# breakout.net
KiCad netlist of a schematic drawn in EAGLE
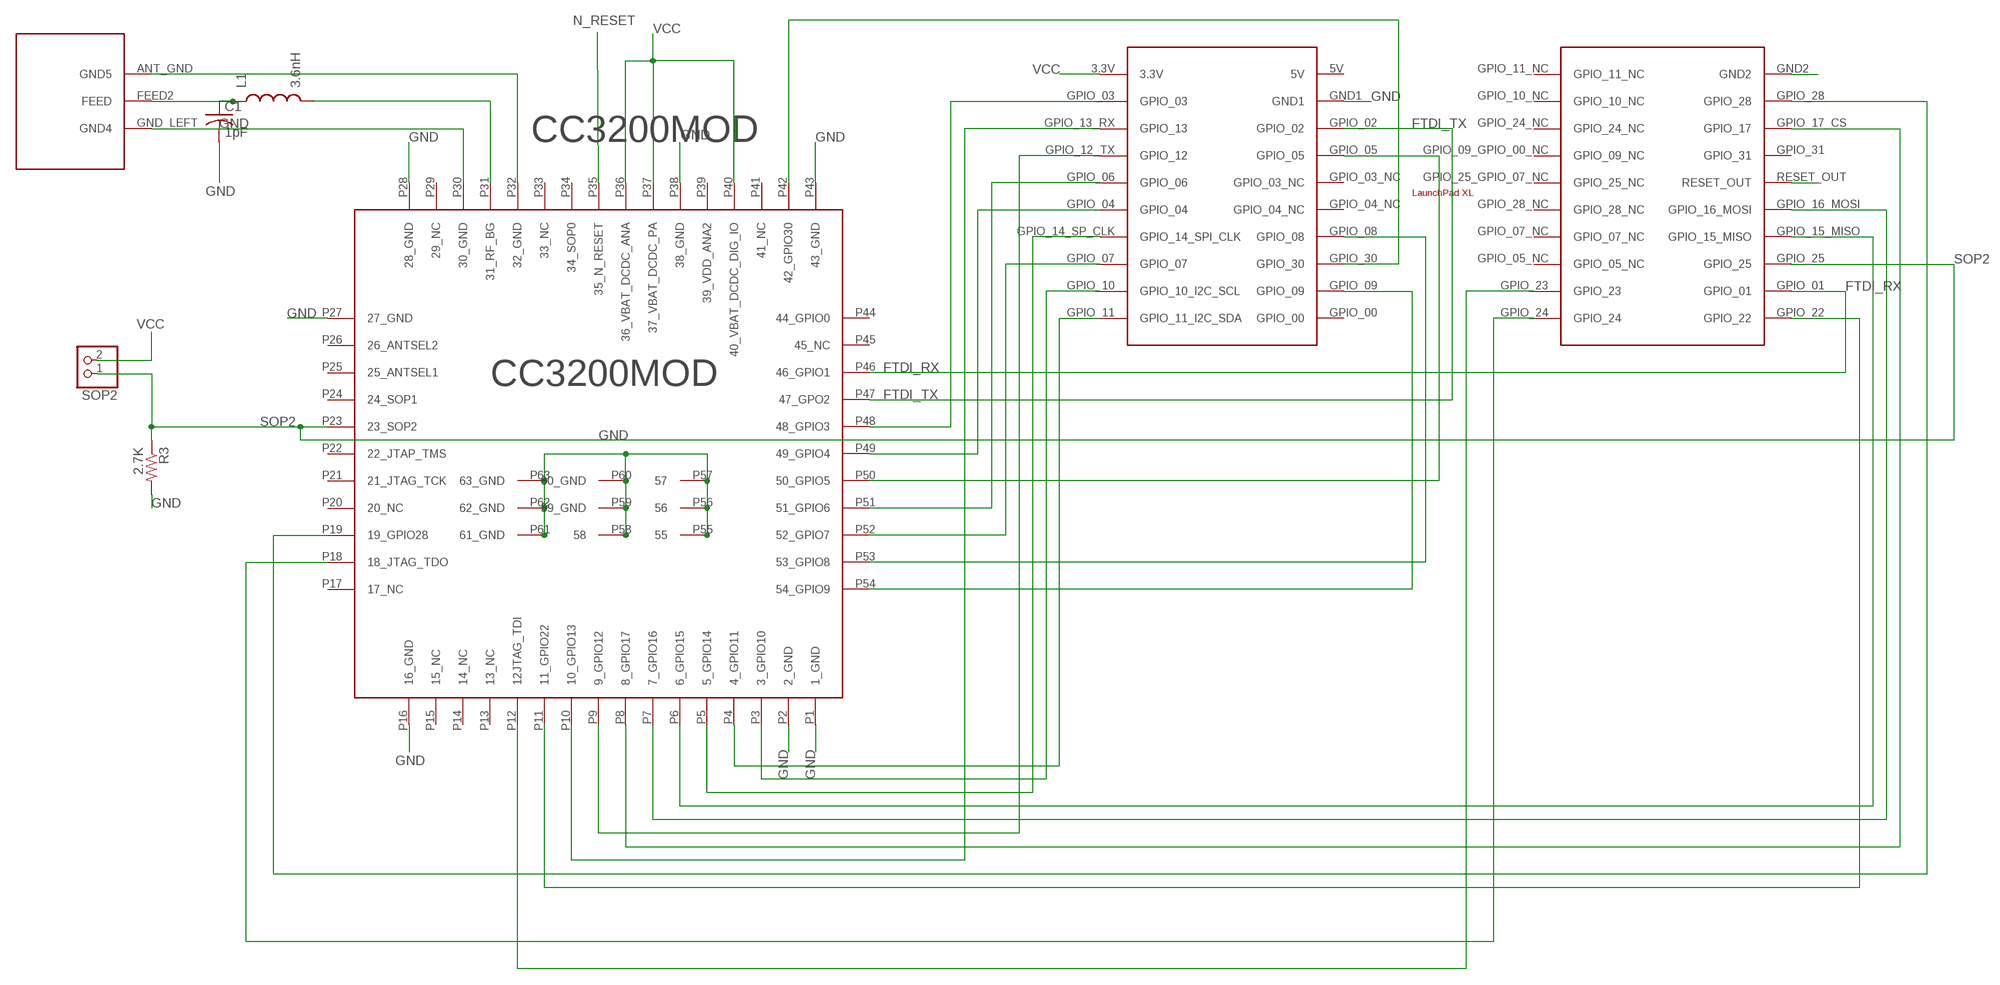
[diagram p0: schematic, sheet 1]
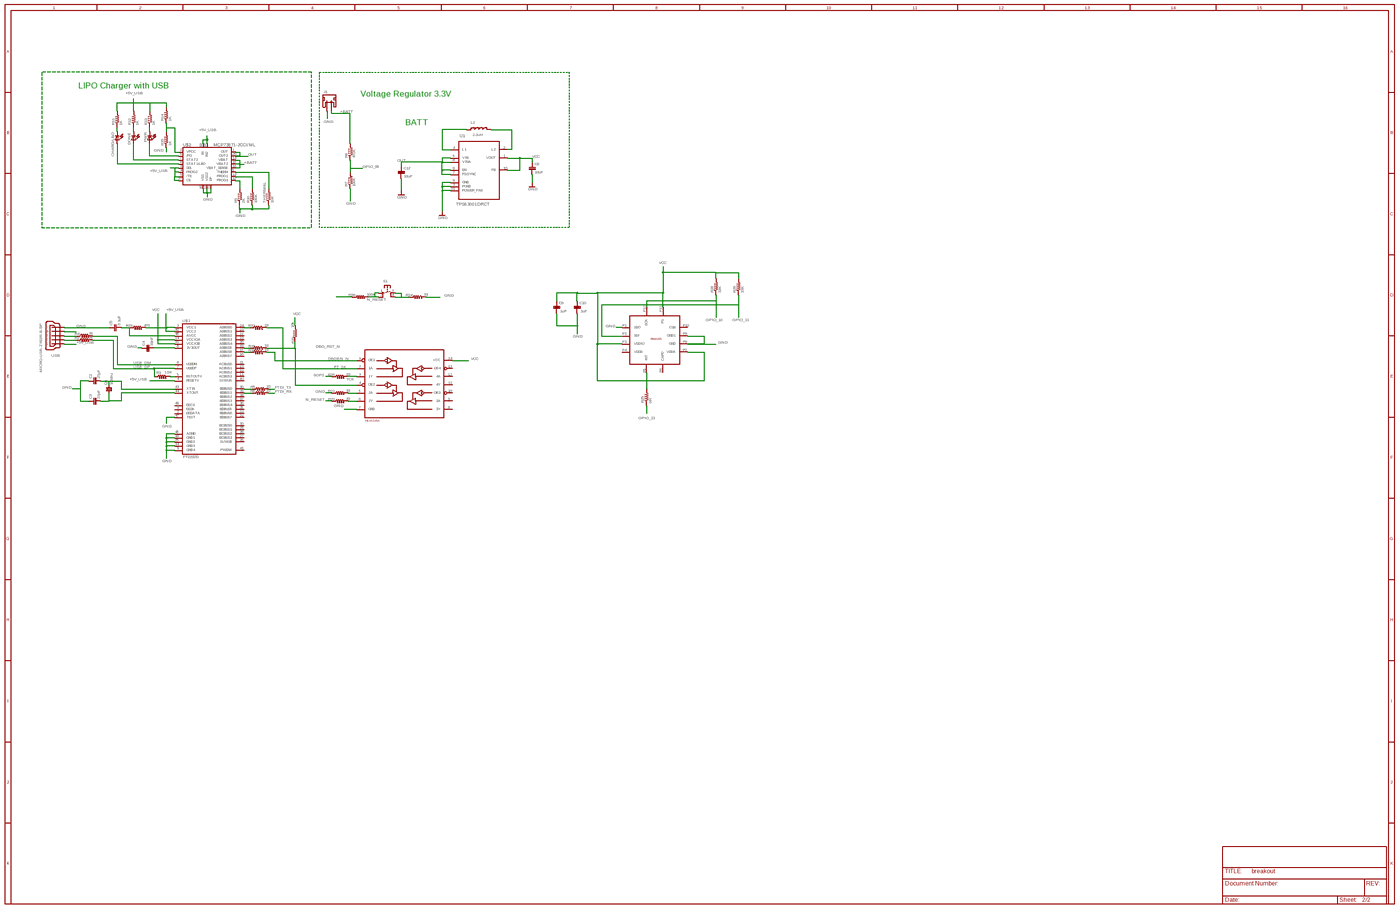
[diagram p1: schematic, sheet 2, overview]
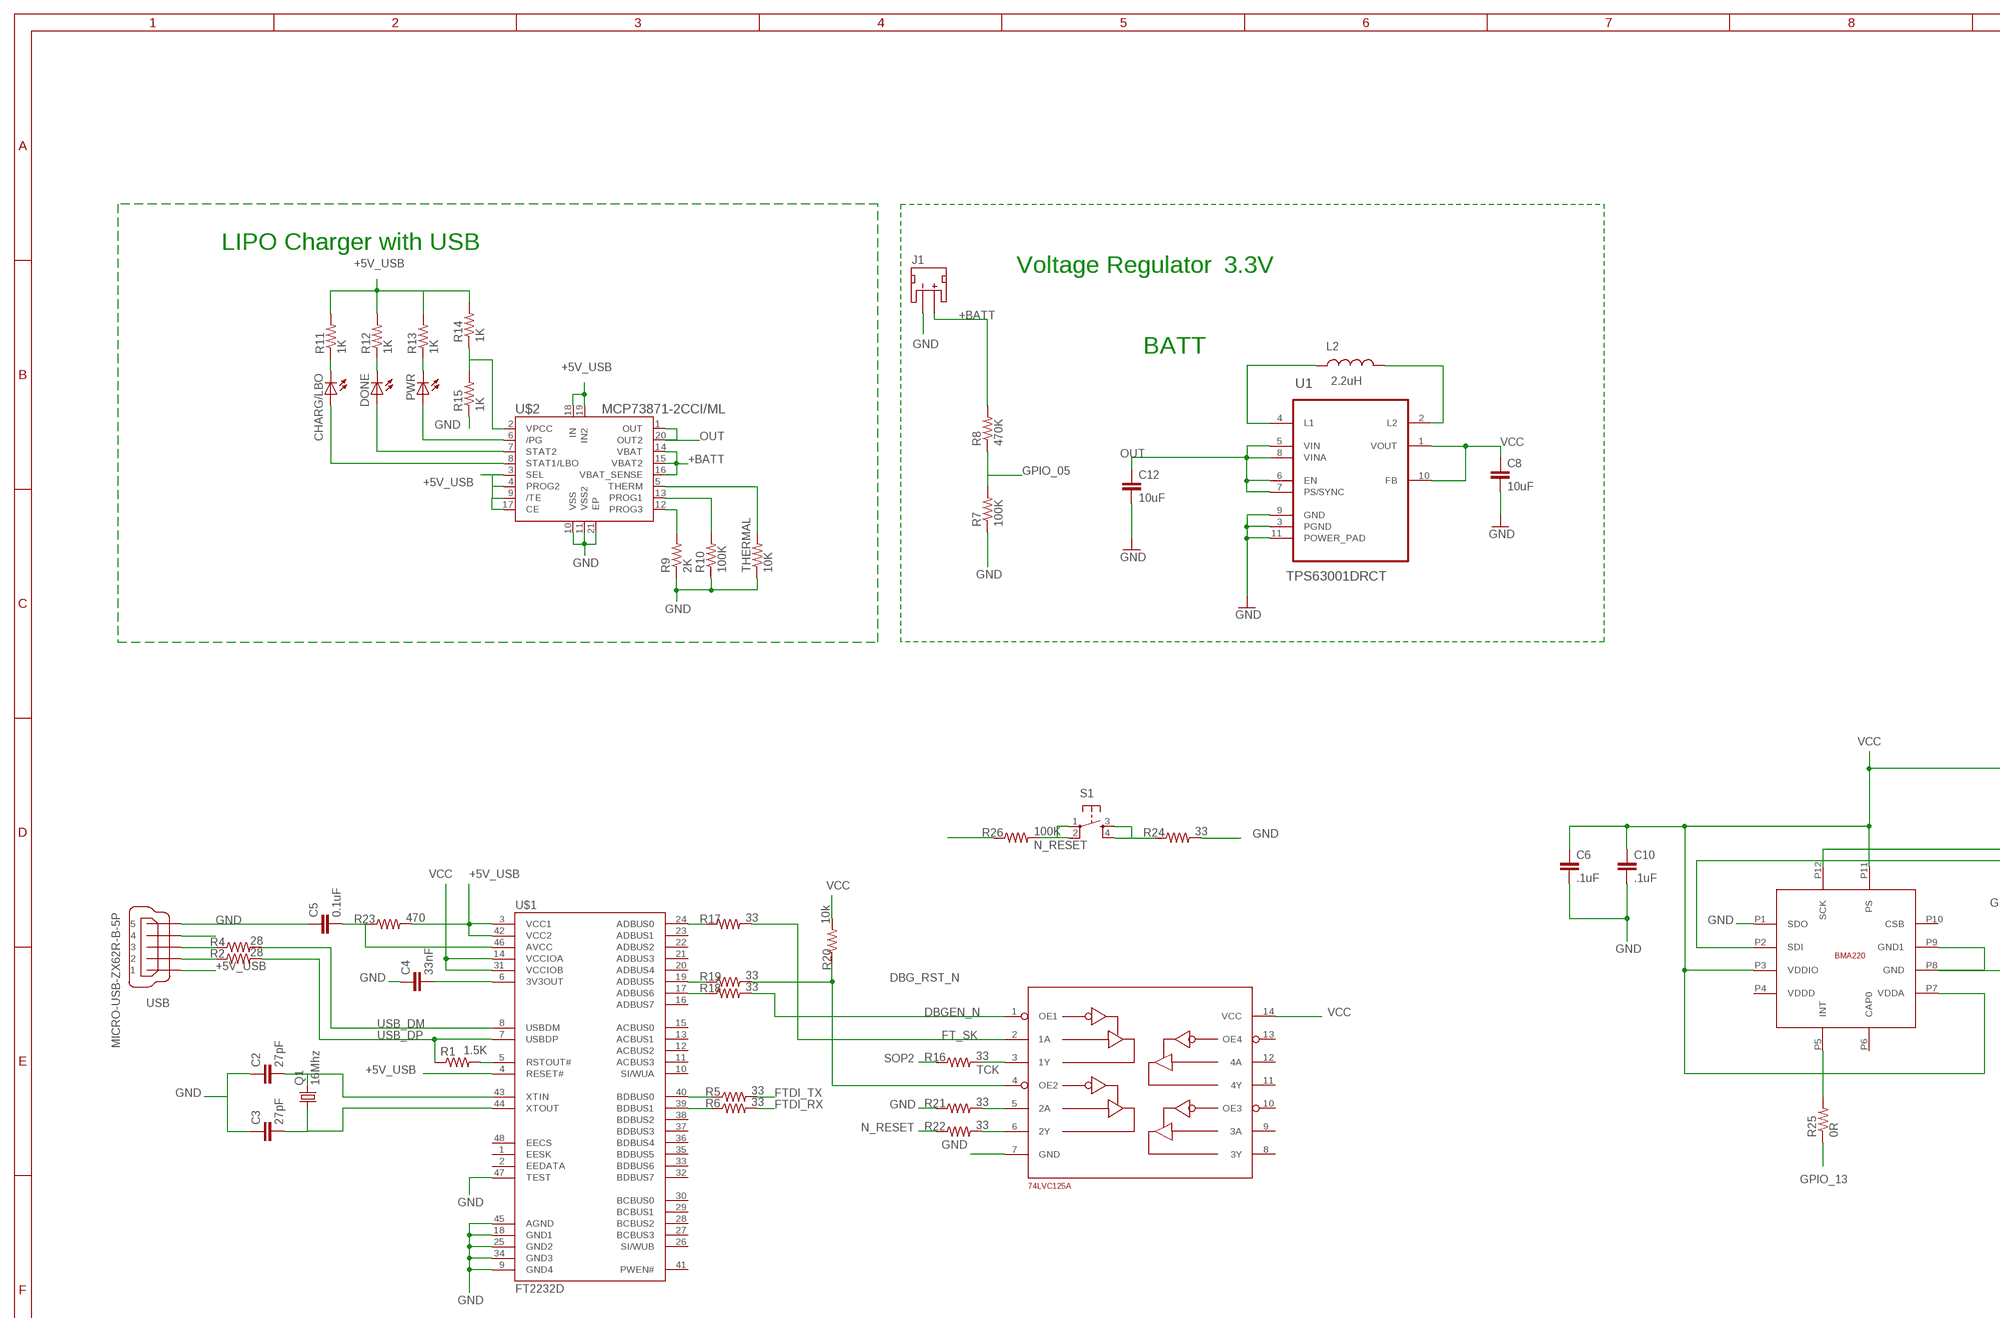
[diagram p2: schematic, sheet 2, part 1 of 4]
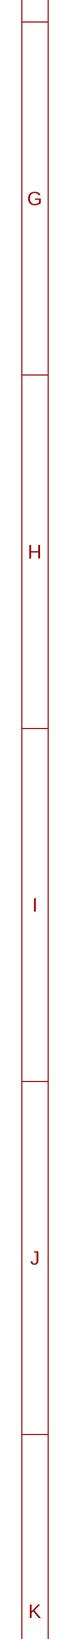
[diagram p3: schematic, sheet 2, part 2 of 4]
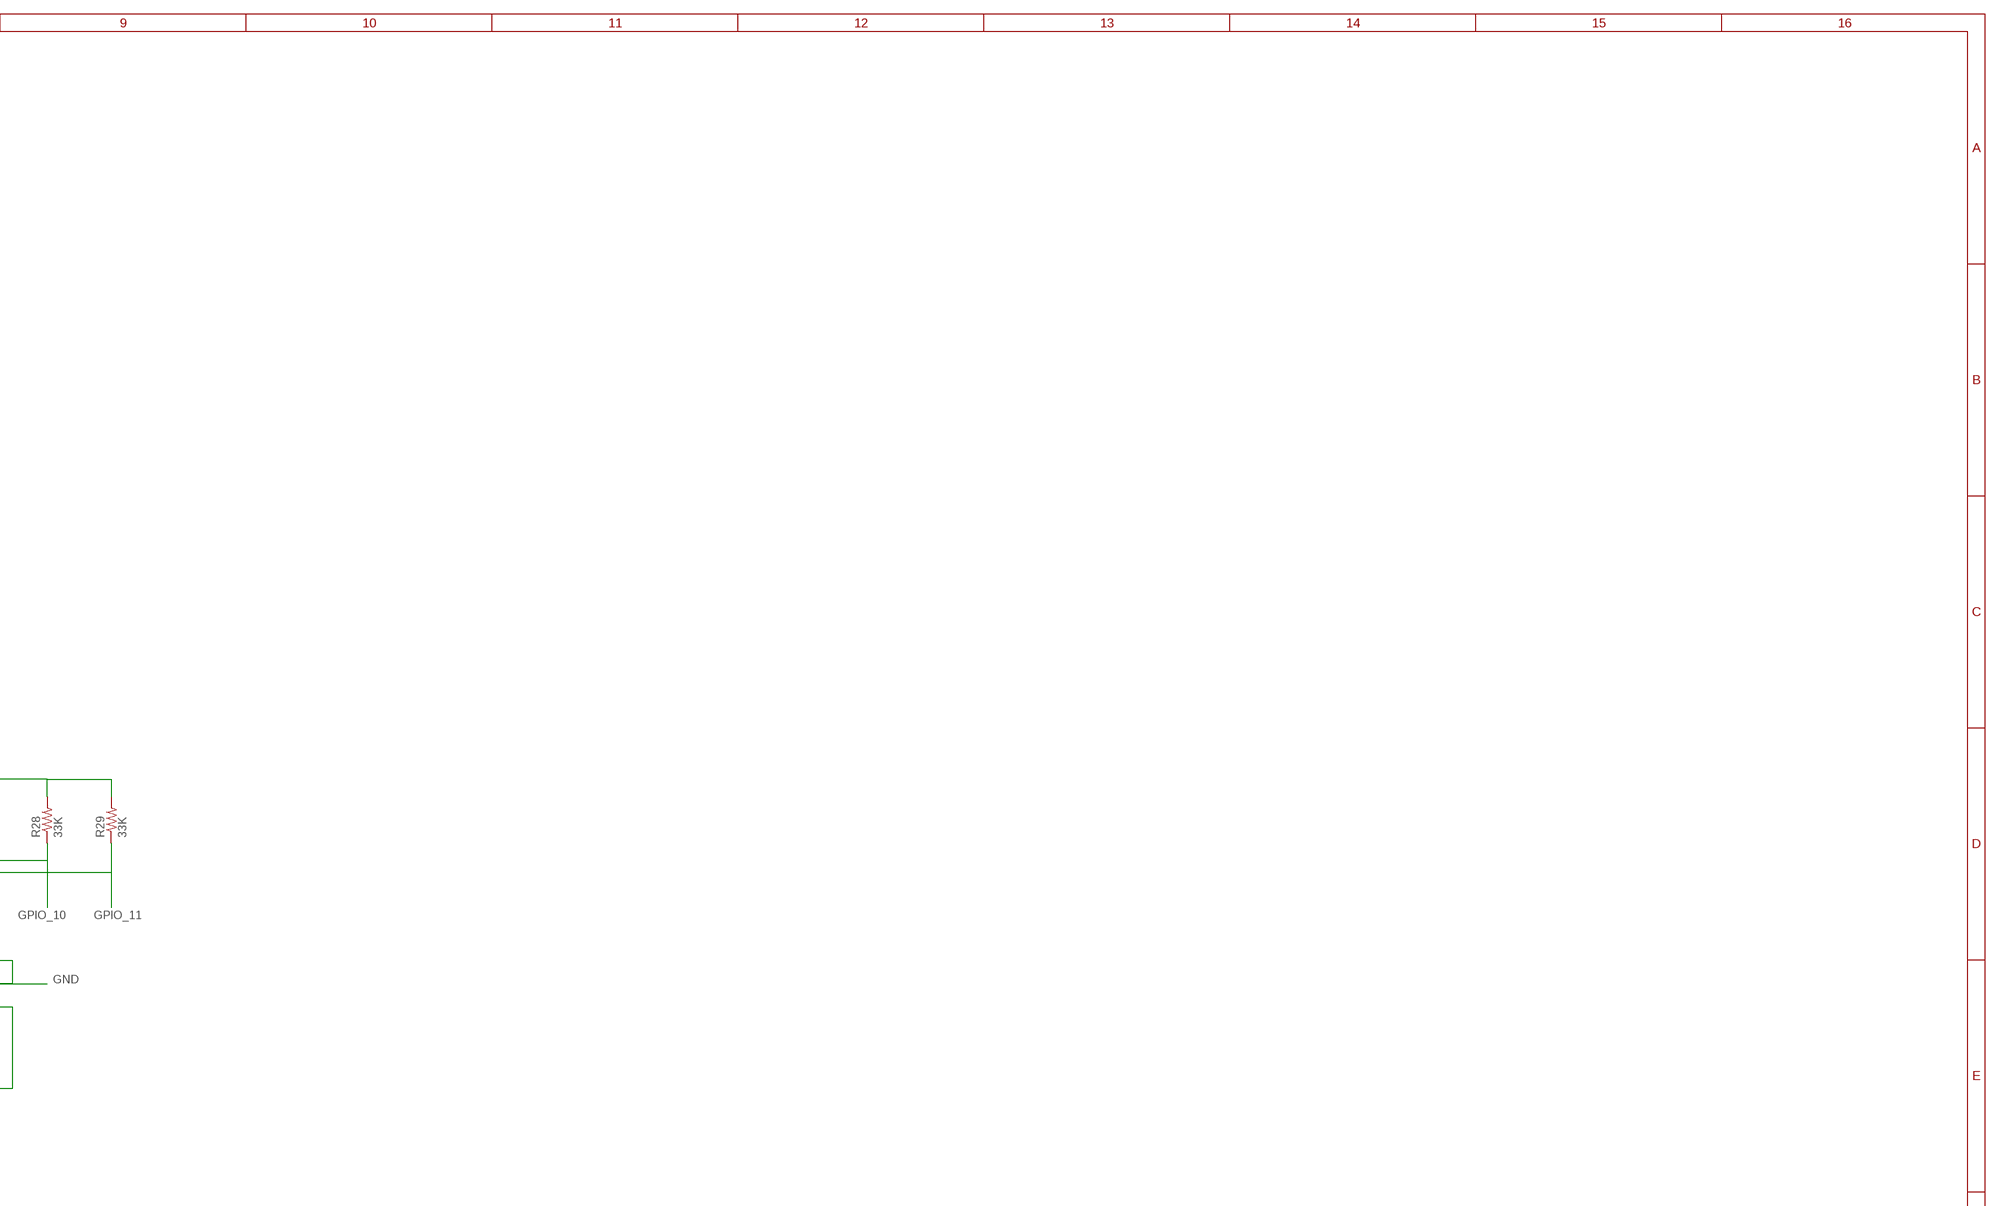
[diagram p4: schematic, sheet 2, part 3 of 4]
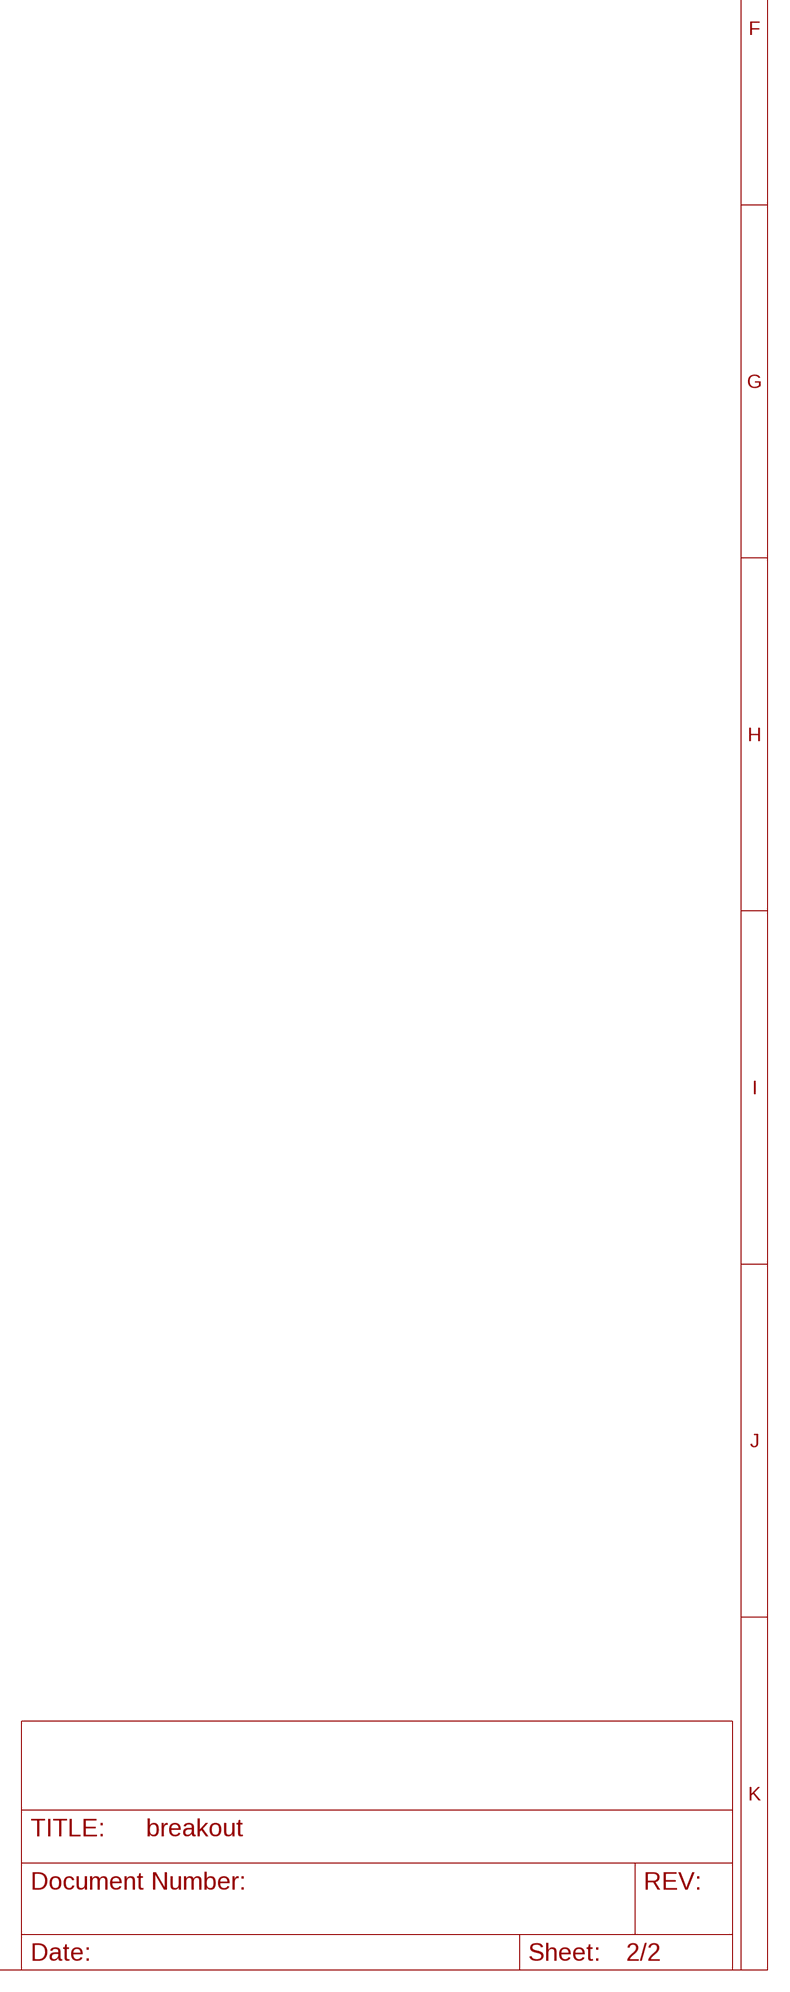
[diagram p5: schematic, sheet 2, part 4 of 4]

(export (version "E")
  (design (tool "Eeschema 10.0.6"))
  (components
    (comp (ref "C2")
      (value "27pF")
      (footprint "eagle-import:0402-CAP")
      (libsource (lib "eagle-import") (part "SparkFun-Passives_CAP0402-CAP"))
    )
    (comp (ref "C3")
      (value "27pF")
      (footprint "eagle-import:0402-CAP")
      (libsource (lib "eagle-import") (part "SparkFun-Passives_CAP0402-CAP"))
    )
    (comp (ref "C4")
      (value "33nF")
      (footprint "eagle-import:0402-CAP")
      (libsource (lib "eagle-import") (part "SparkFun-Passives_CAP0402-CAP"))
    )
    (comp (ref "C5")
      (value "0.1uF")
      (footprint "eagle-import:0402-CAP")
      (libsource (lib "eagle-import") (part "SparkFun-Passives_CAP0402-CAP"))
    )
    (comp (ref "C6")
      (value ".1uF")
      (footprint "eagle-import:0402-CAP")
      (libsource (lib "eagle-import") (part "CAP0402-CAP"))
    )
    (comp (ref "C8")
      (value "10uF")
      (footprint "eagle-import:C0603")
      (libsource (lib "eagle-import") (part "C-EUC0603"))
    )
    (comp (ref "C10")
      (value ".1uF")
      (footprint "eagle-import:0402-CAP")
      (libsource (lib "eagle-import") (part "CAP0402-CAP"))
    )
    (comp (ref "C12")
      (value "10uF")
      (footprint "eagle-import:C0603")
      (libsource (lib "eagle-import") (part "C-EUC0603"))
    )
    (comp (ref "CHARG/LBO")
      (value "LEDSML0603")
      (footprint "eagle-import:SML0603")
      (libsource (lib "eagle-import") (part "LEDSML0603"))
    )
    (comp (ref "DONE")
      (value "LEDSML0603")
      (footprint "eagle-import:SML0603")
      (libsource (lib "eagle-import") (part "LEDSML0603"))
    )
    (comp (ref "J1")
      (value "JST_2MM_MALE")
      (footprint "eagle-import:JST-2-SMD")
      (libsource (lib "eagle-import") (part "JST_2MM_MALE"))
    )
    (comp (ref "L2")
      (value "2.2uH")
      (footprint "eagle-import:0805")
      (libsource (lib "eagle-import") (part "INDUCTOR0805"))
    )
    (comp (ref "PWR")
      (value "LEDSML0603")
      (footprint "eagle-import:SML0603")
      (libsource (lib "eagle-import") (part "LEDSML0603"))
    )
    (comp (ref "Q1")
      (value "16Mhz")
      (footprint "eagle-import:TC26H")
      (libsource (lib "eagle-import") (part "CRYSTALTC26H"))
    )
    (comp (ref "R1")
      (value "1.5K")
      (footprint "eagle-import:0603-RES")
      (libsource (lib "eagle-import") (part "RESISTOR0603"))
    )
    (comp (ref "R2")
      (value "28")
      (footprint "eagle-import:0603-RES")
      (libsource (lib "eagle-import") (part "RESISTOR0603-RES"))
    )
    (comp (ref "R4")
      (value "28")
      (footprint "eagle-import:0603-RES")
      (libsource (lib "eagle-import") (part "RESISTOR0603-RES"))
    )
    (comp (ref "R5")
      (value "33")
      (footprint "eagle-import:0603-RES")
      (libsource (lib "eagle-import") (part "RESISTOR0603"))
    )
    (comp (ref "R6")
      (value "33")
      (footprint "eagle-import:0603-RES")
      (libsource (lib "eagle-import") (part "RESISTOR0603"))
    )
    (comp (ref "R7")
      (value "100K")
      (footprint "eagle-import:0603-RES")
      (libsource (lib "eagle-import") (part "RESISTOR0603"))
    )
    (comp (ref "R8")
      (value "470K")
      (footprint "eagle-import:0603-RES")
      (libsource (lib "eagle-import") (part "RESISTOR0603"))
    )
    (comp (ref "R9")
      (value "2K")
      (footprint "eagle-import:0603-RES")
      (libsource (lib "eagle-import") (part "RESISTOR0603-RES"))
    )
    (comp (ref "R10")
      (value "100K")
      (footprint "eagle-import:0603-RES")
      (libsource (lib "eagle-import") (part "RESISTOR0603-RES"))
    )
    (comp (ref "R11")
      (value "1K")
      (footprint "eagle-import:0603-RES")
      (libsource (lib "eagle-import") (part "RESISTOR0603-RES"))
    )
    (comp (ref "R12")
      (value "1K")
      (footprint "eagle-import:0603-RES")
      (libsource (lib "eagle-import") (part "RESISTOR0603-RES"))
    )
    (comp (ref "R13")
      (value "1K")
      (footprint "eagle-import:0603-RES")
      (libsource (lib "eagle-import") (part "RESISTOR0603-RES"))
    )
    (comp (ref "R14")
      (value "1K")
      (footprint "eagle-import:0603-RES")
      (libsource (lib "eagle-import") (part "RESISTOR0603-RES"))
    )
    (comp (ref "R15")
      (value "1K")
      (footprint "eagle-import:0603-RES")
      (libsource (lib "eagle-import") (part "RESISTOR0603-RES"))
    )
    (comp (ref "R16")
      (value "33")
      (footprint "eagle-import:0603-RES")
      (libsource (lib "eagle-import") (part "RESISTOR0603"))
    )
    (comp (ref "R17")
      (value "33")
      (footprint "eagle-import:0603-RES")
      (libsource (lib "eagle-import") (part "RESISTOR0603"))
    )
    (comp (ref "R18")
      (value "33")
      (footprint "eagle-import:0603-RES")
      (libsource (lib "eagle-import") (part "RESISTOR0603"))
    )
    (comp (ref "R19")
      (value "33")
      (footprint "eagle-import:0603-RES")
      (libsource (lib "eagle-import") (part "RESISTOR0603"))
    )
    (comp (ref "R20")
      (value "10k")
      (footprint "eagle-import:0603-RES")
      (libsource (lib "eagle-import") (part "RESISTOR0603"))
    )
    (comp (ref "R21")
      (value "33")
      (footprint "eagle-import:0603-RES")
      (libsource (lib "eagle-import") (part "RESISTOR0603"))
    )
    (comp (ref "R22")
      (value "33")
      (footprint "eagle-import:0603-RES")
      (libsource (lib "eagle-import") (part "RESISTOR0603"))
    )
    (comp (ref "R23")
      (value "470")
      (footprint "eagle-import:0603-RES")
      (libsource (lib "eagle-import") (part "RESISTOR0603"))
    )
    (comp (ref "R24")
      (value "33")
      (footprint "eagle-import:0603-RES")
      (libsource (lib "eagle-import") (part "RESISTOR0603"))
    )
    (comp (ref "R25")
      (value "0R")
      (footprint "eagle-import:0603-RES")
      (libsource (lib "eagle-import") (part "RESISTOR0603-RES"))
    )
    (comp (ref "R26")
      (value "100K")
      (footprint "eagle-import:0603-RES")
      (libsource (lib "eagle-import") (part "RESISTOR0603"))
    )
    (comp (ref "R28")
      (value "33K")
      (footprint "eagle-import:0402-RES")
      (libsource (lib "eagle-import") (part "RESISTOR0402-RES"))
    )
    (comp (ref "R29")
      (value "33K")
      (footprint "eagle-import:0402-RES")
      (libsource (lib "eagle-import") (part "RESISTOR0402-RES"))
    )
    (comp (ref "S1")
      (value "TAC_SWITCHSMD")
      (footprint "eagle-import:TACTILE_SWITCH_SMD")
      (libsource (lib "eagle-import") (part "TAC_SWITCHSMD"))
    )
    (comp (ref "THERMAL")
      (value "10K")
      (footprint "eagle-import:0603-RES")
      (libsource (lib "eagle-import") (part "RESISTOR0603-RES"))
    )
    (comp (ref "U$1")
      (value "FT2232D")
      (footprint "eagle-import:LQFP-48")
      (libsource (lib "eagle-import") (part "FT2232D"))
    )
    (comp (ref "U$2")
      (value "MCP73871-2CCI/ML")
      (footprint "eagle-import:QFN20-4X4")
      (libsource (lib "eagle-import") (part "MCP73871ML-2CCI/"))
    )
    (comp (ref "U$3")
      (value "DECADE-74LVC125A")
      (footprint "eagle-import:DECADE-SO-14")
      (libsource (lib "eagle-import") (part "DECADE-74LVC125A"))
    )
    (comp (ref "U$4")
      (value "BMA220")
      (footprint "eagle-import:BMA222")
      (libsource (lib "eagle-import") (part "BMA220"))
    )
    (comp (ref "U1")
      (value "TPS63001DRCT")
      (footprint "eagle-import:SON50P300X300X100-11N")
      (libsource (lib "eagle-import") (part "TPS63001DRCT"))
    )
    (comp (ref "USB")
      (value "MICRO-USB-ZX62R-B-5P")
      (footprint "eagle-import:ZX62R-B-5P")
      (libsource (lib "eagle-import") (part "MICRO-USB-ZX62R-B-5P"))
    )
    (comp (ref "ANT_PAD")
      (value "ANT")
      (footprint "eagle-import:ANT")
      (libsource (lib "eagle-import") (part "ANT"))
    )
    (comp (ref "C1")
      (value "1pF")
      (footprint "eagle-import:C0402")
      (libsource (lib "eagle-import") (part "C-USC0402"))
    )
    (comp (ref "CC3200MOD")
      (value "CC3200")
      (footprint "eagle-import:CC3200MOD")
      (libsource (lib "eagle-import") (part "CC3200"))
    )
    (comp (ref "L1")
      (value "3.6nH")
      (footprint "eagle-import:C0402")
      (libsource (lib "eagle-import") (part "INDUCTOR-SPARKFUN0402"))
    )
    (comp (ref "R3")
      (value "2.7K")
      (footprint "eagle-import:0603-RES")
      (libsource (lib "eagle-import") (part "RESISTOR0603"))
    )
    (comp (ref "SOP2")
      (value "PINHD-1X2")
      (footprint "eagle-import:1X02")
      (libsource (lib "eagle-import") (part "PINHD-1X2"))
    )
    (comp (ref "U11")
      (value "XL")
      (footprint "eagle-import:LAUNCHPADXL")
      (libsource (lib "eagle-import") (part "XL"))
    )
  )
  (nets
    (net (code "1") (name "+5V_USB") (class "Default")
      (node (ref "R11") (pin "2") (pinfunction "2_2") (pintype "passive"))
      (node (ref "R12") (pin "2") (pinfunction "2_2") (pintype "passive"))
      (node (ref "R13") (pin "2") (pinfunction "2_2") (pintype "passive"))
      (node (ref "R14") (pin "2") (pinfunction "2_2") (pintype "passive"))
      (node (ref "R23") (pin "2") (pinfunction "2_2") (pintype "passive"))
      (node (ref "U$1") (pin "3") (pinfunction "VCC1_3") (pintype "power_in"))
      (node (ref "U$1") (pin "4") (pinfunction "RESET#_4") (pintype "bidirectional"))
      (node (ref "U$1") (pin "42") (pinfunction "VCC2_42") (pintype "power_in"))
      (node (ref "U$2") (pin "17") (pinfunction "CE_17") (pintype "input"))
      (node (ref "U$2") (pin "18") (pinfunction "IN_18") (pintype "power_in"))
      (node (ref "U$2") (pin "19") (pinfunction "IN2_19") (pintype "power_in"))
      (node (ref "U$2") (pin "3") (pinfunction "SEL_3") (pintype "input"))
      (node (ref "U$2") (pin "4") (pinfunction "PROG2_4") (pintype "input"))
      (node (ref "U$2") (pin "9") (pinfunction "/TE_9") (pintype "input"))
      (node (ref "USB") (pin "1") (pinfunction "1_1") (pintype "input"))
    )
    (net (code "2") (name "+BATT") (class "Default")
      (node (ref "J1") (pin "2") (pinfunction "+_2") (pintype "bidirectional"))
      (node (ref "R8") (pin "2") (pinfunction "2_2") (pintype "passive"))
      (node (ref "U$2") (pin "14") (pinfunction "VBAT_14") (pintype "bidirectional"))
      (node (ref "U$2") (pin "15") (pinfunction "VBAT2_15") (pintype "bidirectional"))
      (node (ref "U$2") (pin "16") (pinfunction "VBAT_SENSE_16") (pintype "bidirectional"))
    )
    (net (code "3") (name "DBGEN_N") (class "Default")
      (node (ref "R18") (pin "2") (pinfunction "2_2") (pintype "passive"))
      (node (ref "U$3") (pin "1") (pinfunction "OE1_1") (pintype "bidirectional"))
    )
    (net (code "4") (name "DBG_RST_N") (class "Default")
      (node (ref "R19") (pin "2") (pinfunction "2_2") (pintype "passive"))
      (node (ref "R20") (pin "1") (pinfunction "1_1") (pintype "passive"))
      (node (ref "U$3") (pin "4") (pinfunction "OE2_4") (pintype "bidirectional"))
    )
    (net (code "5") (name "FTDI_RX") (class "Default")
      (node (ref "CC3200MOD") (pin "P46") (pinfunction "46_GPIO1_P46") (pintype "bidirectional"))
      (node (ref "R6") (pin "2") (pinfunction "2_2") (pintype "passive"))
      (node (ref "U11") (pin "GPIO_01") (pinfunction "GPIO_01_GPIO_01") (pintype "bidirectional"))
    )
    (net (code "6") (name "FTDI_TX") (class "Default")
      (node (ref "CC3200MOD") (pin "P47") (pinfunction "47_GPO2_P47") (pintype "bidirectional"))
      (node (ref "R5") (pin "2") (pinfunction "2_2") (pintype "passive"))
      (node (ref "U11") (pin "GPIO_02") (pinfunction "GPIO_02_GPIO_02") (pintype "bidirectional"))
    )
    (net (code "7") (name "FT_SK") (class "Default")
      (node (ref "R17") (pin "2") (pinfunction "2_2") (pintype "passive"))
      (node (ref "U$3") (pin "2") (pinfunction "1A_2") (pintype "bidirectional"))
    )
    (net (code "8") (name "GND") (class "Default")
      (node (ref "ANT_PAD") (pin "ANT_GND") (pinfunction "GND5_ANT_GND") (pintype "bidirectional"))
      (node (ref "ANT_PAD") (pin "GND_LEFT") (pinfunction "GND4_GND_LEFT") (pintype "bidirectional"))
      (node (ref "C1") (pin "2") (pinfunction "2_2") (pintype "passive"))
      (node (ref "C10") (pin "2") (pinfunction "2_2") (pintype "passive"))
      (node (ref "C12") (pin "2") (pinfunction "2_2") (pintype "passive"))
      (node (ref "C2") (pin "1") (pinfunction "1_1") (pintype "passive"))
      (node (ref "C3") (pin "1") (pinfunction "1_1") (pintype "passive"))
      (node (ref "C4") (pin "1") (pinfunction "1_1") (pintype "passive"))
      (node (ref "C5") (pin "1") (pinfunction "1_1") (pintype "passive"))
      (node (ref "C6") (pin "2") (pinfunction "2_2") (pintype "passive"))
      (node (ref "C8") (pin "2") (pinfunction "2_2") (pintype "passive"))
      (node (ref "CC3200MOD") (pin "P1") (pinfunction "1_GND_P1") (pintype "bidirectional"))
      (node (ref "CC3200MOD") (pin "P16") (pinfunction "16_GND_P16") (pintype "bidirectional"))
      (node (ref "CC3200MOD") (pin "P2") (pinfunction "2_GND_P2") (pintype "bidirectional"))
      (node (ref "CC3200MOD") (pin "P27") (pinfunction "27_GND_P27") (pintype "bidirectional"))
      (node (ref "CC3200MOD") (pin "P28") (pinfunction "28_GND_P28") (pintype "bidirectional"))
      (node (ref "CC3200MOD") (pin "P30") (pinfunction "30_GND_P30") (pintype "bidirectional"))
      (node (ref "CC3200MOD") (pin "P32") (pinfunction "32_GND_P32") (pintype "bidirectional"))
      (node (ref "CC3200MOD") (pin "P38") (pinfunction "38_GND_P38") (pintype "bidirectional"))
      (node (ref "CC3200MOD") (pin "P43") (pinfunction "43_GND_P43") (pintype "bidirectional"))
      (node (ref "CC3200MOD") (pin "P55") (pinfunction "55_P55") (pintype "bidirectional"))
      (node (ref "CC3200MOD") (pin "P56") (pinfunction "56_P56") (pintype "bidirectional"))
      (node (ref "CC3200MOD") (pin "P57") (pinfunction "57_P57") (pintype "bidirectional"))
      (node (ref "CC3200MOD") (pin "P58") (pinfunction "58_P58") (pintype "bidirectional"))
      (node (ref "CC3200MOD") (pin "P59") (pinfunction "59_GND_P59") (pintype "bidirectional"))
      (node (ref "CC3200MOD") (pin "P60") (pinfunction "60_GND_P60") (pintype "bidirectional"))
      (node (ref "CC3200MOD") (pin "P61") (pinfunction "61_GND_P61") (pintype "bidirectional"))
      (node (ref "CC3200MOD") (pin "P62") (pinfunction "62_GND_P62") (pintype "bidirectional"))
      (node (ref "CC3200MOD") (pin "P63") (pinfunction "63_GND_P63") (pintype "bidirectional"))
      (node (ref "J1") (pin "1") (pinfunction "-_1") (pintype "bidirectional"))
      (node (ref "R10") (pin "1") (pinfunction "1_1") (pintype "passive"))
      (node (ref "R15") (pin "1") (pinfunction "1_1") (pintype "passive"))
      (node (ref "R21") (pin "1") (pinfunction "1_1") (pintype "passive"))
      (node (ref "R24") (pin "2") (pinfunction "2_2") (pintype "passive"))
      (node (ref "R3") (pin "2") (pinfunction "2_2") (pintype "passive"))
      (node (ref "R7") (pin "1") (pinfunction "1_1") (pintype "passive"))
      (node (ref "R9") (pin "1") (pinfunction "1_1") (pintype "passive"))
      (node (ref "THERMAL") (pin "1") (pinfunction "1_1") (pintype "passive"))
      (node (ref "U$1") (pin "18") (pinfunction "GND1_18") (pintype "power_in"))
      (node (ref "U$1") (pin "25") (pinfunction "GND2_25") (pintype "power_in"))
      (node (ref "U$1") (pin "34") (pinfunction "GND3_34") (pintype "power_in"))
      (node (ref "U$1") (pin "45") (pinfunction "AGND_45") (pintype "power_in"))
      (node (ref "U$1") (pin "47") (pinfunction "TEST_47") (pintype "input"))
      (node (ref "U$1") (pin "9") (pinfunction "GND4_9") (pintype "bidirectional"))
      (node (ref "U$2") (pin "10") (pinfunction "VSS_10") (pintype "power_in"))
      (node (ref "U$2") (pin "11") (pinfunction "VSS2_11") (pintype "power_in"))
      (node (ref "U$2") (pin "21") (pinfunction "EP_21") (pintype "power_in"))
      (node (ref "U$3") (pin "7") (pinfunction "GND_7") (pintype "bidirectional"))
      (node (ref "U$4") (pin "P1") (pinfunction "SDO_P1") (pintype "bidirectional"))
      (node (ref "U$4") (pin "P8") (pinfunction "GND_P8") (pintype "bidirectional"))
      (node (ref "U$4") (pin "P9") (pinfunction "GND1_P9") (pintype "bidirectional"))
      (node (ref "U1") (pin "11") (pinfunction "POWER_PAD_11") (pintype "passive"))
      (node (ref "U1") (pin "3") (pinfunction "PGND_3") (pintype "passive"))
      (node (ref "U1") (pin "9") (pinfunction "GND_9") (pintype "passive"))
      (node (ref "U11") (pin "GND1") (pinfunction "GND1_GND1") (pintype "bidirectional"))
      (node (ref "U11") (pin "GND2") (pinfunction "GND2_GND2") (pintype "bidirectional"))
      (node (ref "USB") (pin "5") (pinfunction "5_5") (pintype "input"))
    )
    (net (code "9") (name "GPIO_05") (class "Default")
      (node (ref "CC3200MOD") (pin "P50") (pinfunction "50_GPIO5_P50") (pintype "bidirectional"))
      (node (ref "R7") (pin "2") (pinfunction "2_2") (pintype "passive"))
      (node (ref "R8") (pin "1") (pinfunction "1_1") (pintype "passive"))
      (node (ref "U11") (pin "GPIO_05") (pinfunction "GPIO_05_GPIO_05") (pintype "bidirectional"))
    )
    (net (code "10") (name "GPIO_10") (class "Default")
      (node (ref "CC3200MOD") (pin "P3") (pinfunction "3_GPIO10_P3") (pintype "bidirectional"))
      (node (ref "R28") (pin "1") (pinfunction "1_1") (pintype "passive"))
      (node (ref "U$4") (pin "P12") (pinfunction "SCK_P12") (pintype "bidirectional"))
      (node (ref "U11") (pin "GPIO_10") (pinfunction "GPIO_10_I2C_SCL_GPIO_10") (pintype "bidirectional"))
    )
    (net (code "11") (name "GPIO_11") (class "Default")
      (node (ref "CC3200MOD") (pin "P4") (pinfunction "4_GPIO11_P4") (pintype "bidirectional"))
      (node (ref "R29") (pin "1") (pinfunction "1_1") (pintype "passive"))
      (node (ref "U$4") (pin "P2") (pinfunction "SDI_P2") (pintype "bidirectional"))
      (node (ref "U11") (pin "GPIO_11") (pinfunction "GPIO_11_I2C_SDA_GPIO_11") (pintype "bidirectional"))
    )
    (net (code "12") (name "GPIO_13") (class "Default")
      (node (ref "CC3200MOD") (pin "P10") (pinfunction "10_GPIO13_P10") (pintype "bidirectional"))
      (node (ref "R25") (pin "1") (pinfunction "1_1") (pintype "passive"))
      (node (ref "U11") (pin "GPIO_13_RX") (pinfunction "GPIO_13_GPIO_13_RX") (pintype "bidirectional"))
    )
    (net (code "13") (name "N_RESET") (class "Default")
      (node (ref "CC3200MOD") (pin "P35") (pinfunction "35_N_RESET_P35") (pintype "bidirectional"))
      (node (ref "R22") (pin "1") (pinfunction "1_1") (pintype "passive"))
      (node (ref "R26") (pin "2") (pinfunction "2_2") (pintype "passive"))
      (node (ref "S1") (pin "1") (pinfunction "1_1") (pintype "passive"))
      (node (ref "S1") (pin "2") (pinfunction "2_2") (pintype "passive"))
      (node (ref "U11") (pin "RESET_OUT") (pinfunction "RESET_OUT_RESET_OUT") (pintype "bidirectional"))
    )
    (net (code "14") (name "Net-(ANT_PAD-FEED)") (class "Default")
      (node (ref "ANT_PAD") (pin "FEED2") (pinfunction "FEED_FEED2") (pintype "bidirectional"))
      (node (ref "C1") (pin "1") (pinfunction "1_1") (pintype "passive"))
      (node (ref "L1") (pin "1") (pinfunction "1_1") (pintype "passive"))
    )
    (net (code "15") (name "Net-(CC3200MOD-5_GPIO14)") (class "Default")
      (node (ref "CC3200MOD") (pin "P5") (pinfunction "5_GPIO14_P5") (pintype "bidirectional"))
      (node (ref "U11") (pin "GPIO_14_SP_CLK") (pinfunction "GPIO_14_SPI_CLK_GPIO_14_SP_CLK") (pintype "bidirectional"))
    )
    (net (code "16") (name "Net-(CC3200MOD-6_GPIO15)") (class "Default")
      (node (ref "CC3200MOD") (pin "P6") (pinfunction "6_GPIO15_P6") (pintype "bidirectional"))
      (node (ref "U11") (pin "GPIO_15_MISO") (pinfunction "GPIO_15_MISO_GPIO_15_MISO") (pintype "bidirectional"))
    )
    (net (code "17") (name "Net-(CC3200MOD-7_GPIO16)") (class "Default")
      (node (ref "CC3200MOD") (pin "P7") (pinfunction "7_GPIO16_P7") (pintype "bidirectional"))
      (node (ref "U11") (pin "GPIO_16_MOSI") (pinfunction "GPIO_16_MOSI_GPIO_16_MOSI") (pintype "bidirectional"))
    )
    (net (code "18") (name "Net-(CC3200MOD-8_GPIO17)") (class "Default")
      (node (ref "CC3200MOD") (pin "P8") (pinfunction "8_GPIO17_P8") (pintype "bidirectional"))
      (node (ref "U11") (pin "GPIO_17_CS") (pinfunction "GPIO_17_GPIO_17_CS") (pintype "bidirectional"))
    )
    (net (code "19") (name "Net-(CC3200MOD-9_GPIO12)") (class "Default")
      (node (ref "CC3200MOD") (pin "P9") (pinfunction "9_GPIO12_P9") (pintype "bidirectional"))
      (node (ref "U11") (pin "GPIO_12_TX") (pinfunction "GPIO_12_GPIO_12_TX") (pintype "bidirectional"))
    )
    (net (code "20") (name "Net-(CC3200MOD-11_GPIO22)") (class "Default")
      (node (ref "CC3200MOD") (pin "P11") (pinfunction "11_GPIO22_P11") (pintype "bidirectional"))
      (node (ref "U11") (pin "GPIO_22") (pinfunction "GPIO_22_GPIO_22") (pintype "bidirectional"))
    )
    (net (code "21") (name "Net-(CC3200MOD-12JTAG_TDI)") (class "Default")
      (node (ref "CC3200MOD") (pin "P12") (pinfunction "12JTAG_TDI_P12") (pintype "bidirectional"))
      (node (ref "U11") (pin "GPIO_23") (pinfunction "GPIO_23_GPIO_23") (pintype "bidirectional"))
    )
    (net (code "22") (name "Net-(CC3200MOD-18_JTAG_TDO)") (class "Default")
      (node (ref "CC3200MOD") (pin "P18") (pinfunction "18_JTAG_TDO_P18") (pintype "bidirectional"))
      (node (ref "U11") (pin "GPIO_24") (pinfunction "GPIO_24_GPIO_24") (pintype "bidirectional"))
    )
    (net (code "23") (name "Net-(CC3200MOD-19_GPIO28)") (class "Default")
      (node (ref "CC3200MOD") (pin "P19") (pinfunction "19_GPIO28_P19") (pintype "bidirectional"))
      (node (ref "U11") (pin "GPIO_28") (pinfunction "GPIO_28_GPIO_28") (pintype "bidirectional"))
    )
    (net (code "24") (name "Net-(CC3200MOD-31_RF_BG)") (class "Default")
      (node (ref "CC3200MOD") (pin "P31") (pinfunction "31_RF_BG_P31") (pintype "bidirectional"))
      (node (ref "L1") (pin "2") (pinfunction "2_2") (pintype "passive"))
    )
    (net (code "25") (name "Net-(CC3200MOD-42_GPIO30)") (class "Default")
      (node (ref "CC3200MOD") (pin "P42") (pinfunction "42_GPIO30_P42") (pintype "bidirectional"))
      (node (ref "U11") (pin "GPIO_30") (pinfunction "GPIO_30_GPIO_30") (pintype "bidirectional"))
    )
    (net (code "26") (name "Net-(CC3200MOD-48_GPIO3)") (class "Default")
      (node (ref "CC3200MOD") (pin "P48") (pinfunction "48_GPIO3_P48") (pintype "bidirectional"))
      (node (ref "U11") (pin "GPIO_03") (pinfunction "GPIO_03_GPIO_03") (pintype "bidirectional"))
    )
    (net (code "27") (name "Net-(CC3200MOD-49_GPIO4)") (class "Default")
      (node (ref "CC3200MOD") (pin "P49") (pinfunction "49_GPIO4_P49") (pintype "bidirectional"))
      (node (ref "U11") (pin "GPIO_04") (pinfunction "GPIO_04_GPIO_04") (pintype "bidirectional"))
    )
    (net (code "28") (name "Net-(CC3200MOD-51_GPIO6)") (class "Default")
      (node (ref "CC3200MOD") (pin "P51") (pinfunction "51_GPIO6_P51") (pintype "bidirectional"))
      (node (ref "U11") (pin "GPIO_06") (pinfunction "GPIO_06_GPIO_06") (pintype "bidirectional"))
    )
    (net (code "29") (name "Net-(CC3200MOD-52_GPIO7)") (class "Default")
      (node (ref "CC3200MOD") (pin "P52") (pinfunction "52_GPIO7_P52") (pintype "bidirectional"))
      (node (ref "U11") (pin "GPIO_07") (pinfunction "GPIO_07_GPIO_07") (pintype "bidirectional"))
    )
    (net (code "30") (name "Net-(CC3200MOD-53_GPIO8)") (class "Default")
      (node (ref "CC3200MOD") (pin "P53") (pinfunction "53_GPIO8_P53") (pintype "bidirectional"))
      (node (ref "U11") (pin "GPIO_08") (pinfunction "GPIO_08_GPIO_08") (pintype "bidirectional"))
    )
    (net (code "31") (name "Net-(CC3200MOD-54_GPIO9)") (class "Default")
      (node (ref "CC3200MOD") (pin "P54") (pinfunction "54_GPIO9_P54") (pintype "bidirectional"))
      (node (ref "U11") (pin "GPIO_09") (pinfunction "GPIO_09_GPIO_09") (pintype "bidirectional"))
    )
    (net (code "32") (name "Net-(CHARG/LBO-PadC)") (class "Default")
      (node (ref "CHARG/LBO") (pin "C") (pinfunction "C_C") (pintype "passive"))
      (node (ref "R11") (pin "1") (pinfunction "1_1") (pintype "passive"))
    )
    (net (code "33") (name "Net-(DONE-PadC)") (class "Default")
      (node (ref "DONE") (pin "C") (pinfunction "C_C") (pintype "passive"))
      (node (ref "R12") (pin "1") (pinfunction "1_1") (pintype "passive"))
    )
    (net (code "34") (name "Net-(PWR-PadC)") (class "Default")
      (node (ref "PWR") (pin "C") (pinfunction "C_C") (pintype "passive"))
      (node (ref "R13") (pin "1") (pinfunction "1_1") (pintype "passive"))
    )
    (net (code "35") (name "Net-(R2-Pad1)") (class "Default")
      (node (ref "R2") (pin "1") (pinfunction "1_1") (pintype "passive"))
      (node (ref "USB") (pin "2") (pinfunction "2_2") (pintype "input"))
    )
    (net (code "36") (name "Net-(R4-Pad1)") (class "Default")
      (node (ref "R4") (pin "1") (pinfunction "1_1") (pintype "passive"))
      (node (ref "USB") (pin "3") (pinfunction "3_3") (pintype "input"))
    )
    (net (code "37") (name "Net-(R24-Pad1)") (class "Default")
      (node (ref "R24") (pin "1") (pinfunction "1_1") (pintype "passive"))
      (node (ref "S1") (pin "3") (pinfunction "3_3") (pintype "passive"))
      (node (ref "S1") (pin "4") (pinfunction "4_4") (pintype "passive"))
    )
    (net (code "38") (name "Net-(U$1-3V3OUT)") (class "Default")
      (node (ref "C4") (pin "2") (pinfunction "2_2") (pintype "passive"))
      (node (ref "U$1") (pin "6") (pinfunction "3V3OUT_6") (pintype "output"))
    )
    (net (code "39") (name "Net-(U$1-ADBUS0)") (class "Default")
      (node (ref "R17") (pin "1") (pinfunction "1_1") (pintype "passive"))
      (node (ref "U$1") (pin "24") (pinfunction "ADBUS0_24") (pintype "bidirectional"))
    )
    (net (code "40") (name "Net-(U$1-ADBUS5)") (class "Default")
      (node (ref "R19") (pin "1") (pinfunction "1_1") (pintype "passive"))
      (node (ref "U$1") (pin "19") (pinfunction "ADBUS5_19") (pintype "bidirectional"))
    )
    (net (code "41") (name "Net-(U$1-ADBUS6)") (class "Default")
      (node (ref "R18") (pin "1") (pinfunction "1_1") (pintype "passive"))
      (node (ref "U$1") (pin "17") (pinfunction "ADBUS6_17") (pintype "bidirectional"))
    )
    (net (code "42") (name "Net-(U$1-AVCC)") (class "Default")
      (node (ref "C5") (pin "2") (pinfunction "2_2") (pintype "passive"))
      (node (ref "R23") (pin "1") (pinfunction "1_1") (pintype "passive"))
      (node (ref "U$1") (pin "46") (pinfunction "AVCC_46") (pintype "bidirectional"))
    )
    (net (code "43") (name "Net-(U$1-BDBUS0)") (class "Default")
      (node (ref "R5") (pin "1") (pinfunction "1_1") (pintype "passive"))
      (node (ref "U$1") (pin "40") (pinfunction "BDBUS0_40") (pintype "output"))
    )
    (net (code "44") (name "Net-(U$1-BDBUS1)") (class "Default")
      (node (ref "R6") (pin "1") (pinfunction "1_1") (pintype "passive"))
      (node (ref "U$1") (pin "39") (pinfunction "BDBUS1_39") (pintype "input"))
    )
    (net (code "45") (name "Net-(U$1-RSTOUT#)") (class "Default")
      (node (ref "R1") (pin "2") (pinfunction "2_2") (pintype "passive"))
      (node (ref "U$1") (pin "5") (pinfunction "RSTOUT#_5") (pintype "bidirectional"))
    )
    (net (code "46") (name "Net-(U$1-XTIN)") (class "Default")
      (node (ref "C2") (pin "2") (pinfunction "2_2") (pintype "passive"))
      (node (ref "Q1") (pin "2") (pinfunction "2_2") (pintype "passive"))
      (node (ref "U$1") (pin "43") (pinfunction "XTIN_43") (pintype "bidirectional"))
    )
    (net (code "47") (name "Net-(U$1-XTOUT)") (class "Default")
      (node (ref "C3") (pin "2") (pinfunction "2_2") (pintype "passive"))
      (node (ref "Q1") (pin "1") (pinfunction "1_1") (pintype "passive"))
      (node (ref "U$1") (pin "44") (pinfunction "XTOUT_44") (pintype "bidirectional"))
    )
    (net (code "48") (name "Net-(U$2-PROG1)") (class "Default")
      (node (ref "R10") (pin "2") (pinfunction "2_2") (pintype "passive"))
      (node (ref "U$2") (pin "13") (pinfunction "PROG1_13") (pintype "bidirectional"))
    )
    (net (code "49") (name "Net-(U$2-PROG3)") (class "Default")
      (node (ref "R9") (pin "2") (pinfunction "2_2") (pintype "passive"))
      (node (ref "U$2") (pin "12") (pinfunction "PROG3_12") (pintype "bidirectional"))
    )
    (net (code "50") (name "Net-(U$2-STAT1{slash}LBO)") (class "Default")
      (node (ref "CHARG/LBO") (pin "A") (pinfunction "A_A") (pintype "passive"))
      (node (ref "U$2") (pin "8") (pinfunction "STAT1/LBO_8") (pintype "open_collector"))
    )
    (net (code "51") (name "Net-(U$2-STAT2)") (class "Default")
      (node (ref "DONE") (pin "A") (pinfunction "A_A") (pintype "passive"))
      (node (ref "U$2") (pin "7") (pinfunction "STAT2_7") (pintype "open_collector"))
    )
    (net (code "52") (name "Net-(U$2-THERM)") (class "Default")
      (node (ref "THERMAL") (pin "2") (pinfunction "2_2") (pintype "passive"))
      (node (ref "U$2") (pin "5") (pinfunction "THERM_5") (pintype "bidirectional"))
    )
    (net (code "53") (name "Net-(U$2-VPCC)") (class "Default")
      (node (ref "R14") (pin "1") (pinfunction "1_1") (pintype "passive"))
      (node (ref "R15") (pin "2") (pinfunction "2_2") (pintype "passive"))
      (node (ref "U$2") (pin "2") (pinfunction "VPCC_2") (pintype "input"))
    )
    (net (code "54") (name "Net-(U$2-{slash}PG)") (class "Default")
      (node (ref "PWR") (pin "A") (pinfunction "A_A") (pintype "passive"))
      (node (ref "U$2") (pin "6") (pinfunction "/PG_6") (pintype "open_collector"))
    )
    (net (code "55") (name "Net-(U$3-2A)") (class "Default")
      (node (ref "R21") (pin "2") (pinfunction "2_2") (pintype "passive"))
      (node (ref "U$3") (pin "5") (pinfunction "2A_5") (pintype "bidirectional"))
    )
    (net (code "56") (name "Net-(U$3-2Y)") (class "Default")
      (node (ref "R22") (pin "2") (pinfunction "2_2") (pintype "passive"))
      (node (ref "U$3") (pin "6") (pinfunction "2Y_6") (pintype "bidirectional"))
    )
    (net (code "57") (name "Net-(U$4-INT)") (class "Default")
      (node (ref "R25") (pin "2") (pinfunction "2_2") (pintype "passive"))
      (node (ref "U$4") (pin "P5") (pinfunction "INT_P5") (pintype "bidirectional"))
    )
    (net (code "58") (name "Net-(U1-L1)") (class "Default")
      (node (ref "L2") (pin "1") (pinfunction "1_1") (pintype "passive"))
      (node (ref "U1") (pin "4") (pinfunction "L1_4") (pintype "passive"))
    )
    (net (code "59") (name "Net-(U1-L2)") (class "Default")
      (node (ref "L2") (pin "2") (pinfunction "2_2") (pintype "passive"))
      (node (ref "U1") (pin "2") (pinfunction "L2_2") (pintype "passive"))
    )
    (net (code "60") (name "OUT") (class "Default")
      (node (ref "C12") (pin "1") (pinfunction "1_1") (pintype "passive"))
      (node (ref "U$2") (pin "1") (pinfunction "OUT_1") (pintype "power_in"))
      (node (ref "U$2") (pin "20") (pinfunction "OUT2_20") (pintype "power_in"))
      (node (ref "U1") (pin "5") (pinfunction "VIN_5") (pintype "power_in"))
      (node (ref "U1") (pin "6") (pinfunction "EN_6") (pintype "input"))
      (node (ref "U1") (pin "7") (pinfunction "PS/SYNC_7") (pintype "input"))
      (node (ref "U1") (pin "8") (pinfunction "VINA_8") (pintype "power_in"))
    )
    (net (code "61") (name "SOP2") (class "Default")
      (node (ref "CC3200MOD") (pin "P23") (pinfunction "23_SOP2_P23") (pintype "bidirectional"))
      (node (ref "R16") (pin "1") (pinfunction "1_1") (pintype "passive"))
      (node (ref "R3") (pin "1") (pinfunction "1_1") (pintype "passive"))
      (node (ref "SOP2") (pin "1") (pinfunction "1_1") (pintype "passive"))
      (node (ref "U11") (pin "GPIO_25") (pinfunction "GPIO_25_GPIO_25") (pintype "bidirectional"))
    )
    (net (code "62") (name "TCK") (class "Default")
      (node (ref "R16") (pin "2") (pinfunction "2_2") (pintype "passive"))
      (node (ref "U$3") (pin "3") (pinfunction "1Y_3") (pintype "bidirectional"))
    )
    (net (code "63") (name "USB_DM") (class "Default")
      (node (ref "R4") (pin "2") (pinfunction "2_2") (pintype "passive"))
      (node (ref "U$1") (pin "8") (pinfunction "USBDM_8") (pintype "bidirectional"))
    )
    (net (code "64") (name "USB_DP") (class "Default")
      (node (ref "R1") (pin "1") (pinfunction "1_1") (pintype "passive"))
      (node (ref "R2") (pin "2") (pinfunction "2_2") (pintype "passive"))
      (node (ref "U$1") (pin "7") (pinfunction "USBDP_7") (pintype "bidirectional"))
    )
    (net (code "65") (name "VCC") (class "Default")
      (node (ref "C10") (pin "1") (pinfunction "1_1") (pintype "passive"))
      (node (ref "C6") (pin "1") (pinfunction "1_1") (pintype "passive"))
      (node (ref "C8") (pin "1") (pinfunction "1_1") (pintype "passive"))
      (node (ref "CC3200MOD") (pin "P36") (pinfunction "36_VBAT_DCDC_ANA_P36") (pintype "bidirectional"))
      (node (ref "CC3200MOD") (pin "P37") (pinfunction "37_VBAT_DCDC_PA_P37") (pintype "bidirectional"))
      (node (ref "CC3200MOD") (pin "P40") (pinfunction "40_VBAT_DCDC_DIG_IO_P40") (pintype "bidirectional"))
      (node (ref "R20") (pin "2") (pinfunction "2_2") (pintype "passive"))
      (node (ref "R26") (pin "1") (pinfunction "1_1") (pintype "passive"))
      (node (ref "R28") (pin "2") (pinfunction "2_2") (pintype "passive"))
      (node (ref "R29") (pin "2") (pinfunction "2_2") (pintype "passive"))
      (node (ref "SOP2") (pin "2") (pinfunction "2_2") (pintype "passive"))
      (node (ref "U$1") (pin "14") (pinfunction "VCCIOA_14") (pintype "power_in"))
      (node (ref "U$1") (pin "31") (pinfunction "VCCIOB_31") (pintype "bidirectional"))
      (node (ref "U$3") (pin "14") (pinfunction "VCC_14") (pintype "bidirectional"))
      (node (ref "U$4") (pin "P11") (pinfunction "PS_P11") (pintype "bidirectional"))
      (node (ref "U$4") (pin "P3") (pinfunction "VDDIO_P3") (pintype "bidirectional"))
      (node (ref "U$4") (pin "P7") (pinfunction "VDDA_P7") (pintype "bidirectional"))
      (node (ref "U1") (pin "1") (pinfunction "VOUT_1") (pintype "output"))
      (node (ref "U1") (pin "10") (pinfunction "FB_10") (pintype "input"))
      (node (ref "U11") (pin "3.3V") (pinfunction "3.3V_3.3V") (pintype "bidirectional"))
    )
    (net (code "66") (name "unconnected-(CC3200MOD-13_NC-PadP13)") (class "Default")
      (node (ref "CC3200MOD") (pin "P13") (pinfunction "13_NC_P13") (pintype "bidirectional"))
    )
    (net (code "67") (name "unconnected-(CC3200MOD-14_NC-PadP14)") (class "Default")
      (node (ref "CC3200MOD") (pin "P14") (pinfunction "14_NC_P14") (pintype "bidirectional"))
    )
    (net (code "68") (name "unconnected-(CC3200MOD-15_NC-PadP15)") (class "Default")
      (node (ref "CC3200MOD") (pin "P15") (pinfunction "15_NC_P15") (pintype "bidirectional"))
    )
    (net (code "69") (name "unconnected-(CC3200MOD-17_NC-PadP17)") (class "Default")
      (node (ref "CC3200MOD") (pin "P17") (pinfunction "17_NC_P17") (pintype "bidirectional"))
    )
    (net (code "70") (name "unconnected-(CC3200MOD-20_NC-PadP20)") (class "Default")
      (node (ref "CC3200MOD") (pin "P20") (pinfunction "20_NC_P20") (pintype "bidirectional"))
    )
    (net (code "71") (name "unconnected-(CC3200MOD-21_JTAG_TCK-PadP21)") (class "Default")
      (node (ref "CC3200MOD") (pin "P21") (pinfunction "21_JTAG_TCK_P21") (pintype "bidirectional"))
    )
    (net (code "72") (name "unconnected-(CC3200MOD-22_JTAP_TMS-PadP22)") (class "Default")
      (node (ref "CC3200MOD") (pin "P22") (pinfunction "22_JTAP_TMS_P22") (pintype "bidirectional"))
    )
    (net (code "73") (name "unconnected-(CC3200MOD-24_SOP1-PadP24)") (class "Default")
      (node (ref "CC3200MOD") (pin "P24") (pinfunction "24_SOP1_P24") (pintype "bidirectional"))
    )
    (net (code "74") (name "unconnected-(CC3200MOD-25_ANTSEL1-PadP25)") (class "Default")
      (node (ref "CC3200MOD") (pin "P25") (pinfunction "25_ANTSEL1_P25") (pintype "bidirectional"))
    )
    (net (code "75") (name "unconnected-(CC3200MOD-26_ANTSEL2-PadP26)") (class "Default")
      (node (ref "CC3200MOD") (pin "P26") (pinfunction "26_ANTSEL2_P26") (pintype "bidirectional"))
    )
    (net (code "76") (name "unconnected-(CC3200MOD-29_NC-PadP29)") (class "Default")
      (node (ref "CC3200MOD") (pin "P29") (pinfunction "29_NC_P29") (pintype "bidirectional"))
    )
    (net (code "77") (name "unconnected-(CC3200MOD-33_NC-PadP33)") (class "Default")
      (node (ref "CC3200MOD") (pin "P33") (pinfunction "33_NC_P33") (pintype "bidirectional"))
    )
    (net (code "78") (name "unconnected-(CC3200MOD-34_SOP0-PadP34)") (class "Default")
      (node (ref "CC3200MOD") (pin "P34") (pinfunction "34_SOP0_P34") (pintype "bidirectional"))
    )
    (net (code "79") (name "unconnected-(CC3200MOD-39_VDD_ANA2-PadP39)") (class "Default")
      (node (ref "CC3200MOD") (pin "P39") (pinfunction "39_VDD_ANA2_P39") (pintype "bidirectional"))
    )
    (net (code "80") (name "unconnected-(CC3200MOD-41_NC-PadP41)") (class "Default")
      (node (ref "CC3200MOD") (pin "P41") (pinfunction "41_NC_P41") (pintype "bidirectional"))
    )
    (net (code "81") (name "unconnected-(CC3200MOD-44_GPIO0-PadP44)") (class "Default")
      (node (ref "CC3200MOD") (pin "P44") (pinfunction "44_GPIO0_P44") (pintype "bidirectional"))
    )
    (net (code "82") (name "unconnected-(CC3200MOD-45_NC-PadP45)") (class "Default")
      (node (ref "CC3200MOD") (pin "P45") (pinfunction "45_NC_P45") (pintype "bidirectional"))
    )
    (net (code "83") (name "unconnected-(J1-PAD1-PadNC1)") (class "Default")
      (node (ref "J1") (pin "NC1") (pinfunction "PAD1_NC1") (pintype "bidirectional"))
    )
    (net (code "84") (name "unconnected-(J1-PAD2-PadNC2)") (class "Default")
      (node (ref "J1") (pin "NC2") (pinfunction "PAD2_NC2") (pintype "bidirectional"))
    )
    (net (code "85") (name "unconnected-(U$1-ACBUS0-Pad15)") (class "Default")
      (node (ref "U$1") (pin "15") (pinfunction "ACBUS0_15") (pintype "bidirectional"))
    )
    (net (code "86") (name "unconnected-(U$1-ACBUS1-Pad13)") (class "Default")
      (node (ref "U$1") (pin "13") (pinfunction "ACBUS1_13") (pintype "bidirectional"))
    )
    (net (code "87") (name "unconnected-(U$1-ACBUS2-Pad12)") (class "Default")
      (node (ref "U$1") (pin "12") (pinfunction "ACBUS2_12") (pintype "bidirectional"))
    )
    (net (code "88") (name "unconnected-(U$1-ACBUS3-Pad11)") (class "Default")
      (node (ref "U$1") (pin "11") (pinfunction "ACBUS3_11") (pintype "bidirectional"))
    )
    (net (code "89") (name "unconnected-(U$1-ADBUS1-Pad23)") (class "Default")
      (node (ref "U$1") (pin "23") (pinfunction "ADBUS1_23") (pintype "bidirectional"))
    )
    (net (code "90") (name "unconnected-(U$1-ADBUS2-Pad22)") (class "Default")
      (node (ref "U$1") (pin "22") (pinfunction "ADBUS2_22") (pintype "bidirectional"))
    )
    (net (code "91") (name "unconnected-(U$1-ADBUS3-Pad21)") (class "Default")
      (node (ref "U$1") (pin "21") (pinfunction "ADBUS3_21") (pintype "bidirectional"))
    )
    (net (code "92") (name "unconnected-(U$1-ADBUS4-Pad20)") (class "Default")
      (node (ref "U$1") (pin "20") (pinfunction "ADBUS4_20") (pintype "bidirectional"))
    )
    (net (code "93") (name "unconnected-(U$1-ADBUS7-Pad16)") (class "Default")
      (node (ref "U$1") (pin "16") (pinfunction "ADBUS7_16") (pintype "bidirectional"))
    )
    (net (code "94") (name "unconnected-(U$1-BCBUS0-Pad30)") (class "Default")
      (node (ref "U$1") (pin "30") (pinfunction "BCBUS0_30") (pintype "bidirectional"))
    )
    (net (code "95") (name "unconnected-(U$1-BCBUS1-Pad29)") (class "Default")
      (node (ref "U$1") (pin "29") (pinfunction "BCBUS1_29") (pintype "bidirectional"))
    )
    (net (code "96") (name "unconnected-(U$1-BCBUS2-Pad28)") (class "Default")
      (node (ref "U$1") (pin "28") (pinfunction "BCBUS2_28") (pintype "bidirectional"))
    )
    (net (code "97") (name "unconnected-(U$1-BCBUS3-Pad27)") (class "Default")
      (node (ref "U$1") (pin "27") (pinfunction "BCBUS3_27") (pintype "bidirectional"))
    )
    (net (code "98") (name "unconnected-(U$1-BDBUS2-Pad38)") (class "Default")
      (node (ref "U$1") (pin "38") (pinfunction "BDBUS2_38") (pintype "output"))
    )
    (net (code "99") (name "unconnected-(U$1-BDBUS3-Pad37)") (class "Default")
      (node (ref "U$1") (pin "37") (pinfunction "BDBUS3_37") (pintype "input"))
    )
    (net (code "100") (name "unconnected-(U$1-BDBUS4-Pad36)") (class "Default")
      (node (ref "U$1") (pin "36") (pinfunction "BDBUS4_36") (pintype "output"))
    )
    (net (code "101") (name "unconnected-(U$1-BDBUS5-Pad35)") (class "Default")
      (node (ref "U$1") (pin "35") (pinfunction "BDBUS5_35") (pintype "input"))
    )
    (net (code "102") (name "unconnected-(U$1-BDBUS6-Pad33)") (class "Default")
      (node (ref "U$1") (pin "33") (pinfunction "BDBUS6_33") (pintype "input"))
    )
    (net (code "103") (name "unconnected-(U$1-BDBUS7-Pad32)") (class "Default")
      (node (ref "U$1") (pin "32") (pinfunction "BDBUS7_32") (pintype "input"))
    )
    (net (code "104") (name "unconnected-(U$1-EECS-Pad48)") (class "Default")
      (node (ref "U$1") (pin "48") (pinfunction "EECS_48") (pintype "bidirectional"))
    )
    (net (code "105") (name "unconnected-(U$1-EEDATA-Pad2)") (class "Default")
      (node (ref "U$1") (pin "2") (pinfunction "EEDATA_2") (pintype "bidirectional"))
    )
    (net (code "106") (name "unconnected-(U$1-EESK-Pad1)") (class "Default")
      (node (ref "U$1") (pin "1") (pinfunction "EESK_1") (pintype "bidirectional"))
    )
    (net (code "107") (name "unconnected-(U$1-PWEN#-Pad41)") (class "Default")
      (node (ref "U$1") (pin "41") (pinfunction "PWEN#_41") (pintype "bidirectional"))
    )
    (net (code "108") (name "unconnected-(U$1-SI{slash}WUA-Pad10)") (class "Default")
      (node (ref "U$1") (pin "10") (pinfunction "SI/WUA_10") (pintype "bidirectional"))
    )
    (net (code "109") (name "unconnected-(U$1-SI{slash}WUB-Pad26)") (class "Default")
      (node (ref "U$1") (pin "26") (pinfunction "SI/WUB_26") (pintype "bidirectional"))
    )
    (net (code "110") (name "unconnected-(U$3-3A-Pad9)") (class "Default")
      (node (ref "U$3") (pin "9") (pinfunction "3A_9") (pintype "bidirectional"))
    )
    (net (code "111") (name "unconnected-(U$3-3Y-Pad8)") (class "Default")
      (node (ref "U$3") (pin "8") (pinfunction "3Y_8") (pintype "bidirectional"))
    )
    (net (code "112") (name "unconnected-(U$3-4A-Pad12)") (class "Default")
      (node (ref "U$3") (pin "12") (pinfunction "4A_12") (pintype "bidirectional"))
    )
    (net (code "113") (name "unconnected-(U$3-4Y-Pad11)") (class "Default")
      (node (ref "U$3") (pin "11") (pinfunction "4Y_11") (pintype "bidirectional"))
    )
    (net (code "114") (name "unconnected-(U$3-OE3-Pad10)") (class "Default")
      (node (ref "U$3") (pin "10") (pinfunction "OE3_10") (pintype "bidirectional"))
    )
    (net (code "115") (name "unconnected-(U$3-OE4-Pad13)") (class "Default")
      (node (ref "U$3") (pin "13") (pinfunction "OE4_13") (pintype "bidirectional"))
    )
    (net (code "116") (name "unconnected-(U$4-CAP0-PadP6)") (class "Default")
      (node (ref "U$4") (pin "P6") (pinfunction "CAP0_P6") (pintype "bidirectional"))
    )
    (net (code "117") (name "unconnected-(U$4-CSB-PadP10)") (class "Default")
      (node (ref "U$4") (pin "P10") (pinfunction "CSB_P10") (pintype "bidirectional"))
    )
    (net (code "118") (name "unconnected-(U$4-VDDD-PadP4)") (class "Default")
      (node (ref "U$4") (pin "P4") (pinfunction "VDDD_P4") (pintype "bidirectional"))
    )
    (net (code "119") (name "unconnected-(U11-GPIO_09_NC-PadGPIO_09_GPIO_00_NC)") (class "Default")
      (node (ref "U11") (pin "GPIO_09_GPIO_00_NC") (pinfunction "GPIO_09_NC_GPIO_09_GPIO_00_NC") (pintype "bidirectional"))
    )
    (net (code "120") (name "unconnected-(U11-GPIO_25_NC-PadGPIO_25_GPIO_07_NC)") (class "Default")
      (node (ref "U11") (pin "GPIO_25_GPIO_07_NC") (pinfunction "GPIO_25_NC_GPIO_25_GPIO_07_NC") (pintype "bidirectional"))
    )
    (net (code "121") (name "unconnected-(U11-Pad5V)") (class "Default")
      (node (ref "U11") (pin "5V") (pinfunction "5V_5V") (pintype "bidirectional"))
    )
    (net (code "122") (name "unconnected-(U11-PadGPIO_00)") (class "Default")
      (node (ref "U11") (pin "GPIO_00") (pinfunction "GPIO_00_GPIO_00") (pintype "bidirectional"))
    )
    (net (code "123") (name "unconnected-(U11-PadGPIO_03_NC)") (class "Default")
      (node (ref "U11") (pin "GPIO_03_NC") (pinfunction "GPIO_03_NC_GPIO_03_NC") (pintype "bidirectional"))
    )
    (net (code "124") (name "unconnected-(U11-PadGPIO_04_NC)") (class "Default")
      (node (ref "U11") (pin "GPIO_04_NC") (pinfunction "GPIO_04_NC_GPIO_04_NC") (pintype "bidirectional"))
    )
    (net (code "125") (name "unconnected-(U11-PadGPIO_05_NC)") (class "Default")
      (node (ref "U11") (pin "GPIO_05_NC") (pinfunction "GPIO_05_NC_GPIO_05_NC") (pintype "bidirectional"))
    )
    (net (code "126") (name "unconnected-(U11-PadGPIO_07_NC)") (class "Default")
      (node (ref "U11") (pin "GPIO_07_NC") (pinfunction "GPIO_07_NC_GPIO_07_NC") (pintype "bidirectional"))
    )
    (net (code "127") (name "unconnected-(U11-PadGPIO_10_NC)") (class "Default")
      (node (ref "U11") (pin "GPIO_10_NC") (pinfunction "GPIO_10_NC_GPIO_10_NC") (pintype "bidirectional"))
    )
    (net (code "128") (name "unconnected-(U11-PadGPIO_11_NC)") (class "Default")
      (node (ref "U11") (pin "GPIO_11_NC") (pinfunction "GPIO_11_NC_GPIO_11_NC") (pintype "bidirectional"))
    )
    (net (code "129") (name "unconnected-(U11-PadGPIO_24_NC)") (class "Default")
      (node (ref "U11") (pin "GPIO_24_NC") (pinfunction "GPIO_24_NC_GPIO_24_NC") (pintype "bidirectional"))
    )
    (net (code "130") (name "unconnected-(U11-PadGPIO_28_NC)") (class "Default")
      (node (ref "U11") (pin "GPIO_28_NC") (pinfunction "GPIO_28_NC_GPIO_28_NC") (pintype "bidirectional"))
    )
    (net (code "131") (name "unconnected-(U11-PadGPIO_31)") (class "Default")
      (node (ref "U11") (pin "GPIO_31") (pinfunction "GPIO_31_GPIO_31") (pintype "bidirectional"))
    )
    (net (code "132") (name "unconnected-(USB-Pad4)") (class "Default")
      (node (ref "USB") (pin "4") (pinfunction "4_4") (pintype "input"))
    )
  )
)
